# Rear_left_lamp_v4.net
KiCad netlist of a schematic drawn in EAGLE
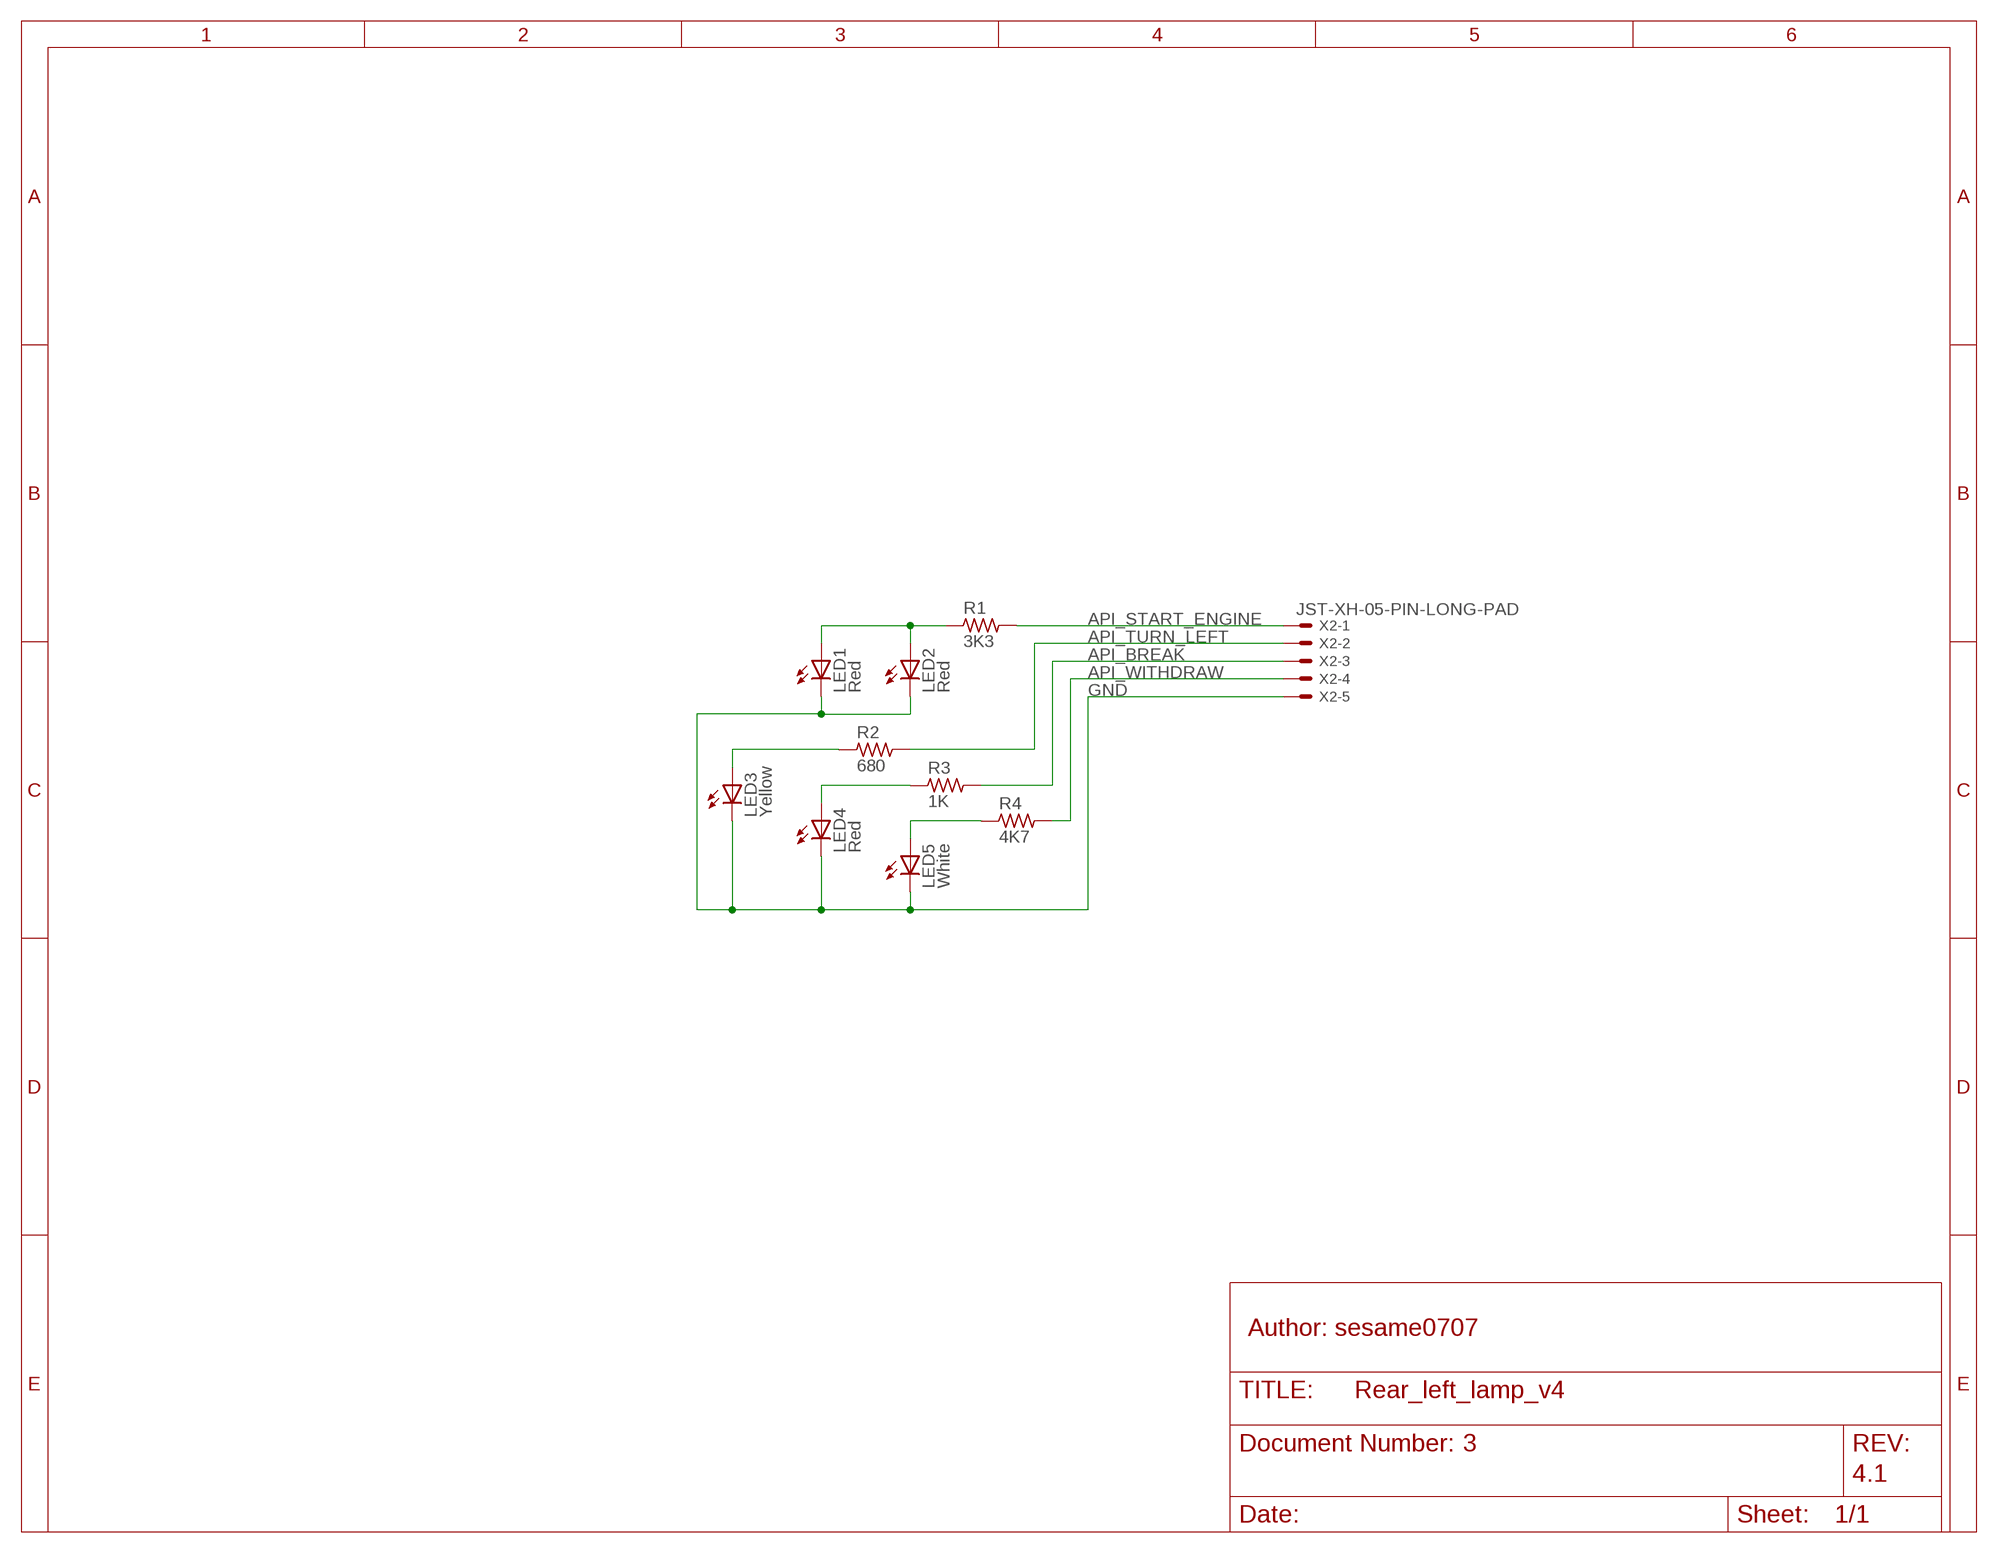
[diagram p0: schematic, sheet 1]

(export (version "E")
  (design (tool "Eeschema 10.0.6"))
  (components
    (comp (ref "LED1")
      (value "Red")
      (footprint "eagle-import:LED5MM")
      (fields
        (field (name "MANUFACTURER") "LUCKYLIGHT")
        (field (name "MANUFACTURER_PART_NUMBER") "LL-503VD2E-1B")
      )
      (libsource (lib "eagle-import") (part "LED5MM"))
    )
    (comp (ref "LED2")
      (value "Red")
      (footprint "eagle-import:LED5MM")
      (fields
        (field (name "MANUFACTURER") "LUCKYLIGHT")
        (field (name "MANUFACTURER_PART_NUMBER") "LL-503VD2E-1B")
      )
      (libsource (lib "eagle-import") (part "LED5MM"))
    )
    (comp (ref "LED3")
      (value "Yellow")
      (footprint "eagle-import:LED5MM")
      (fields
        (field (name "MANUFACTURER") "LUCKYLIGHT")
        (field (name "MANUFACTURER_PART_NUMBER") "LL-503YD2E-1B")
      )
      (libsource (lib "eagle-import") (part "LED5MM"))
    )
    (comp (ref "LED4")
      (value "Red")
      (footprint "eagle-import:LED5MM")
      (fields
        (field (name "MANUFACTURER") "LUCKYLIGHT")
        (field (name "MANUFACTURER_PART_NUMBER") "LL-503VD2E-1B")
      )
      (libsource (lib "eagle-import") (part "LED5MM"))
    )
    (comp (ref "LED5")
      (value "White")
      (footprint "eagle-import:LED5MM")
      (fields
        (field (name "MANUFACTURER") "LUCKYLIGHT")
        (field (name "MANUFACTURER_PART_NUMBER") "LL-504WC2V-W2-3PD")
      )
      (libsource (lib "eagle-import") (part "LED5MM"))
    )
    (comp (ref "R1")
      (value "3K3")
      (footprint "eagle-import:R1206")
      (fields
        (field (name "MANUFACTURER") "ROYAL OHM")
        (field (name "MANUFACTURER_PART_NUMBER") "1206S4J0332T5E")
      )
      (libsource (lib "eagle-import") (part "R_1206"))
    )
    (comp (ref "R2")
      (value "680")
      (footprint "eagle-import:R1206")
      (fields
        (field (name "MANUFACTURER") "ROYAL OHM")
        (field (name "MANUFACTURER_PART_NUMBER") "1206S4J0681T5E")
      )
      (libsource (lib "eagle-import") (part "R_1206"))
    )
    (comp (ref "R3")
      (value "1K")
      (footprint "eagle-import:R1206")
      (fields
        (field (name "MANUFACTURER") "ROYAL OHM")
        (field (name "MANUFACTURER_PART_NUMBER") "1206S4J0102T5E")
      )
      (libsource (lib "eagle-import") (part "R_1206"))
    )
    (comp (ref "R4")
      (value "4K7")
      (footprint "eagle-import:R1206")
      (fields
        (field (name "MANUFACTURER") "ROYAL OHM")
        (field (name "MANUFACTURER_PART_NUMBER") "1206S4J0472T5E")
      )
      (libsource (lib "eagle-import") (part "R_1206"))
    )
    (comp (ref "X2")
      (value "JST-XH-05-PIN-LONG-PAD")
      (footprint "eagle-import:JST-XH-05-PACKAGE-LONG-PAD")
      (libsource (lib "eagle-import") (part "JST-XH-05-PIN-LONG-PAD"))
    )
  )
  (nets
    (net (code "1") (name "/API_BREAK") (class "Default")
      (node (ref "R3") (pin "2") (pinfunction "2_2") (pintype "passive"))
      (node (ref "X2") (pin "3") (pinfunction "S_3") (pintype "passive"))
    )
    (net (code "2") (name "/API_START_ENGINE") (class "Default")
      (node (ref "LED1") (pin "A") (pinfunction "A_A") (pintype "passive"))
      (node (ref "LED2") (pin "A") (pinfunction "A_A") (pintype "passive"))
      (node (ref "R1") (pin "1") (pinfunction "1_1") (pintype "passive"))
    )
    (net (code "3") (name "/API_TURN_LEFT") (class "Default")
      (node (ref "R2") (pin "2") (pinfunction "2_2") (pintype "passive"))
      (node (ref "X2") (pin "2") (pinfunction "S_2") (pintype "passive"))
    )
    (net (code "4") (name "/API_WITHDRAW") (class "Default")
      (node (ref "R4") (pin "2") (pinfunction "2_2") (pintype "passive"))
      (node (ref "X2") (pin "4") (pinfunction "S_4") (pintype "passive"))
    )
    (net (code "5") (name "/GND") (class "Default")
      (node (ref "LED1") (pin "K") (pinfunction "C_K") (pintype "passive"))
      (node (ref "LED2") (pin "K") (pinfunction "C_K") (pintype "passive"))
      (node (ref "LED3") (pin "K") (pinfunction "C_K") (pintype "passive"))
      (node (ref "LED4") (pin "K") (pinfunction "C_K") (pintype "passive"))
      (node (ref "LED5") (pin "K") (pinfunction "C_K") (pintype "passive"))
      (node (ref "X2") (pin "5") (pinfunction "S_5") (pintype "passive"))
    )
    (net (code "6") (name "Net-(LED3-PadA)") (class "Default")
      (node (ref "LED3") (pin "A") (pinfunction "A_A") (pintype "passive"))
      (node (ref "R2") (pin "1") (pinfunction "1_1") (pintype "passive"))
    )
    (net (code "7") (name "Net-(LED4-PadA)") (class "Default")
      (node (ref "LED4") (pin "A") (pinfunction "A_A") (pintype "passive"))
      (node (ref "R3") (pin "1") (pinfunction "1_1") (pintype "passive"))
    )
    (net (code "8") (name "Net-(LED5-PadA)") (class "Default")
      (node (ref "LED5") (pin "A") (pinfunction "A_A") (pintype "passive"))
      (node (ref "R4") (pin "1") (pinfunction "1_1") (pintype "passive"))
    )
    (net (code "9") (name "Net-(X2A-S)") (class "Default")
      (node (ref "R1") (pin "2") (pinfunction "2_2") (pintype "passive"))
      (node (ref "X2") (pin "1") (pinfunction "S_1") (pintype "passive"))
    )
  )
)
